# PROC.net
KiCad netlist of a schematic drawn in Altium Designer
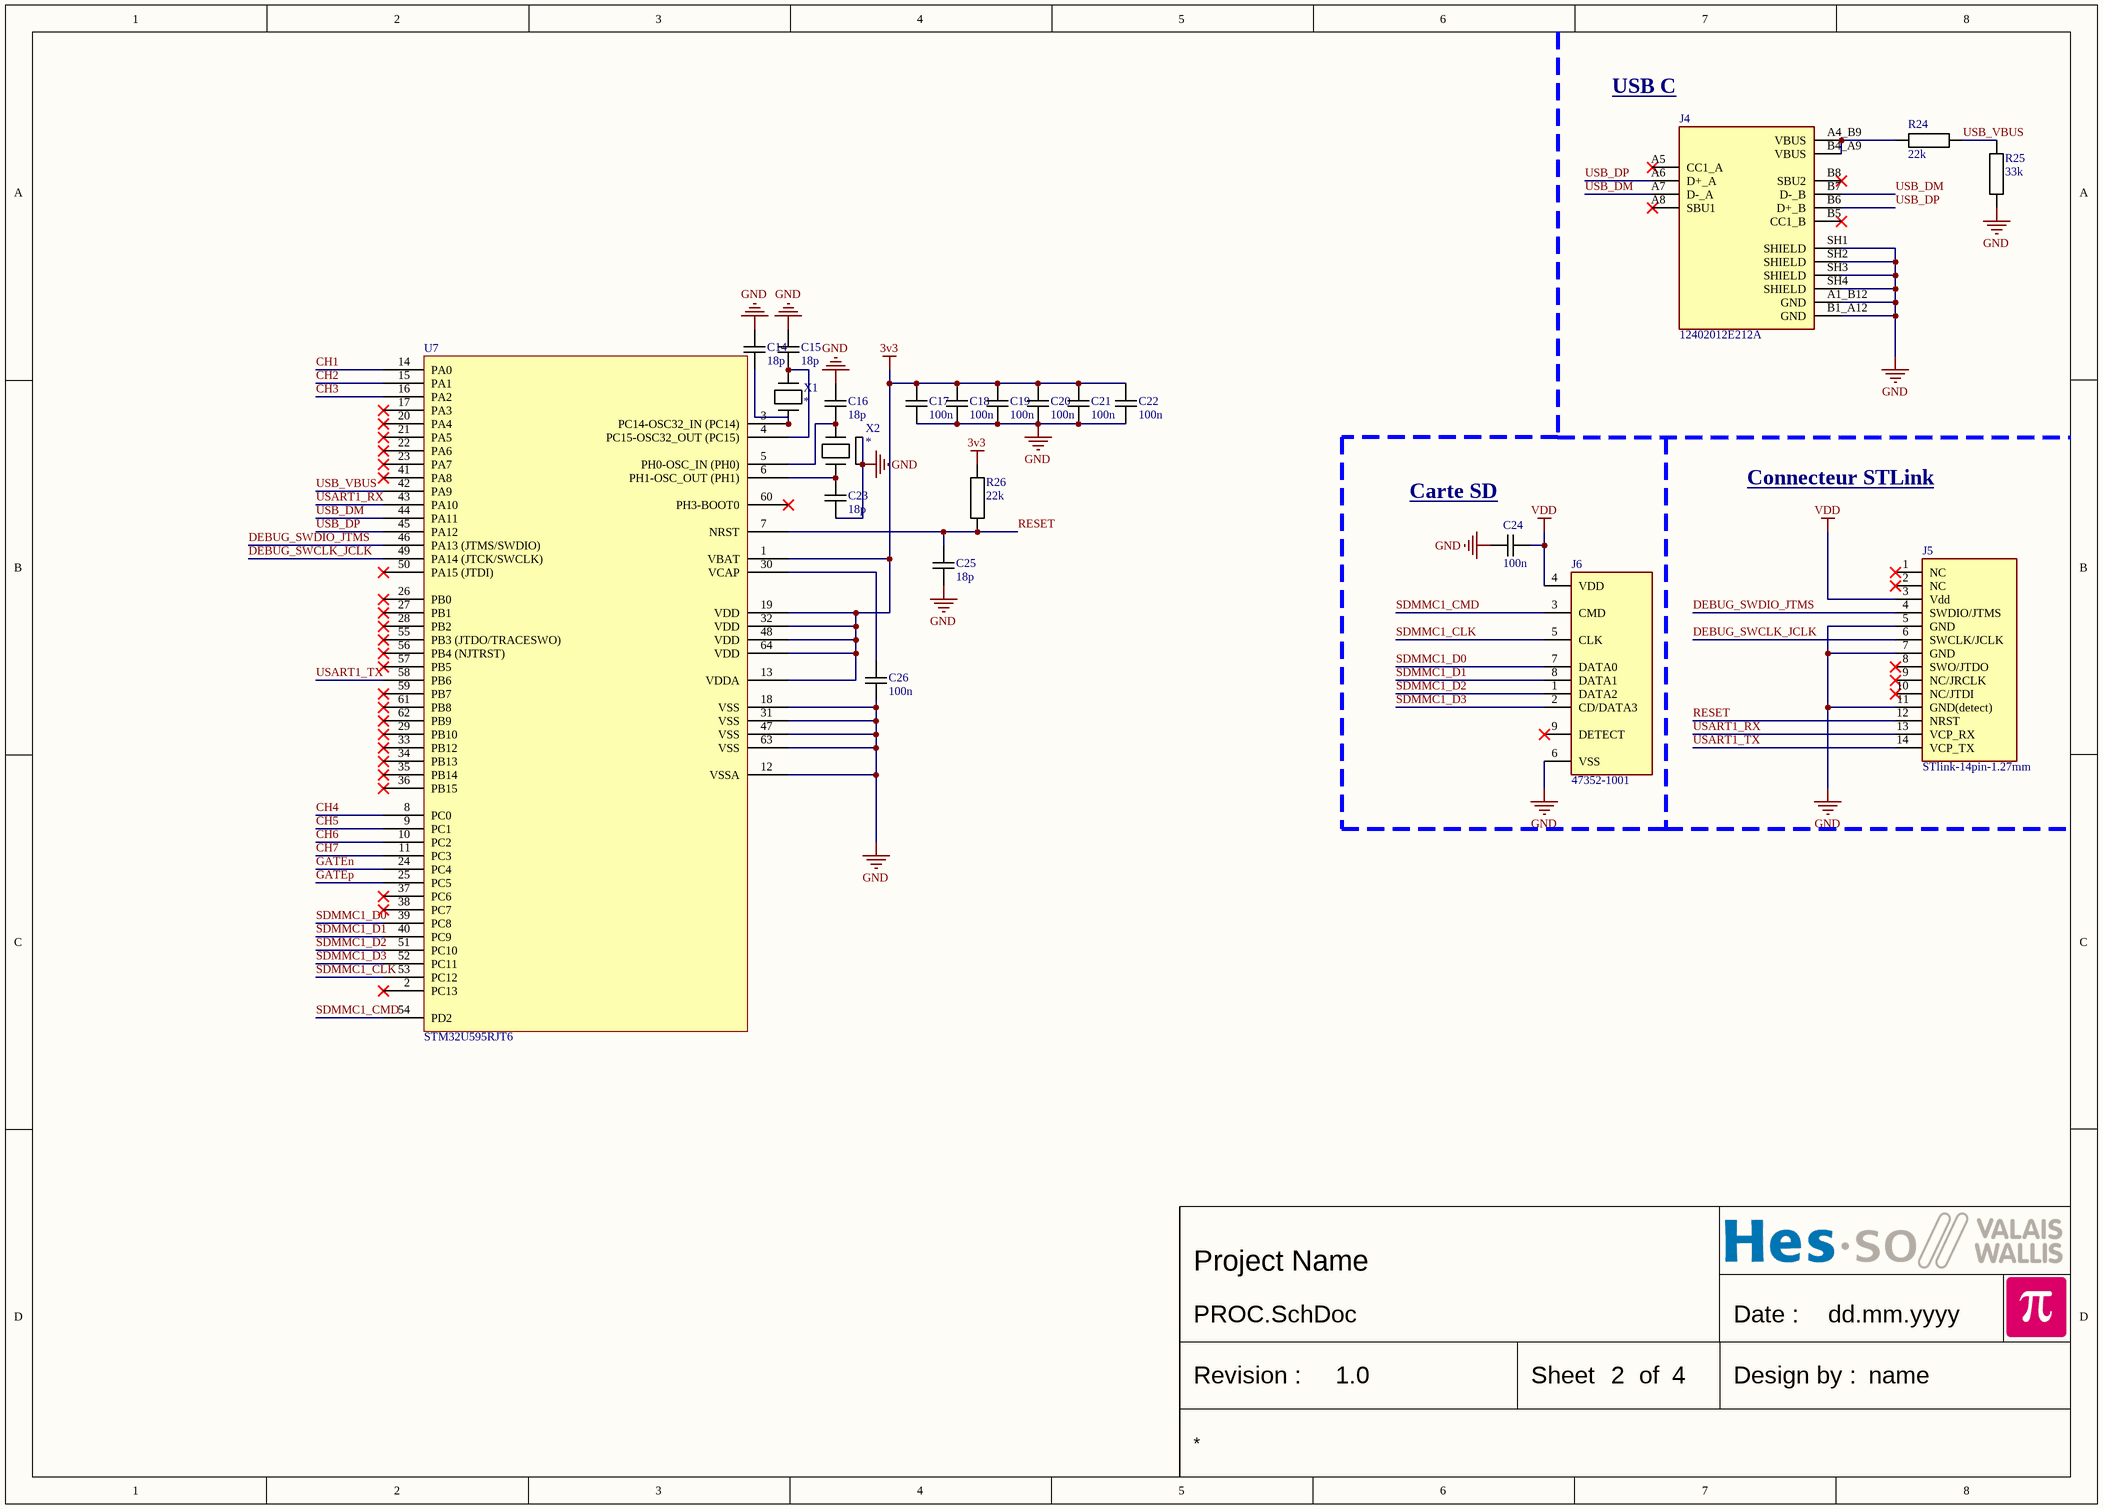
[diagram p0: PROC.SchDoc]

(export (version "E")
  (design (tool "Eeschema 10.0.6"))
  (components
    (comp (ref "C14")
      (value "18p")
      (footprint "CAPACITOR 1005 REFLOW")
      (description "Capacitor")
      (libsource (lib "Capacitor") (part "Capacitor"))
    )
    (comp (ref "C15")
      (value "18p")
      (footprint "CAPACITOR 1005 REFLOW")
      (description "Capacitor")
      (libsource (lib "Capacitor") (part "Capacitor"))
    )
    (comp (ref "C16")
      (value "18p")
      (footprint "CAPACITOR 1005 REFLOW")
      (description "Capacitor")
      (libsource (lib "Capacitor") (part "Capacitor"))
    )
    (comp (ref "C17")
      (value "100n")
      (footprint "CAPACITOR 1005 REFLOW")
      (description "Capacitor")
      (libsource (lib "Capacitor") (part "Capacitor"))
    )
    (comp (ref "C18")
      (value "100n")
      (footprint "CAPACITOR 1005 REFLOW")
      (description "Capacitor")
      (libsource (lib "Capacitor") (part "Capacitor"))
    )
    (comp (ref "C19")
      (value "100n")
      (footprint "CAPACITOR 1005 REFLOW")
      (description "Capacitor")
      (libsource (lib "Capacitor") (part "Capacitor"))
    )
    (comp (ref "C20")
      (value "100n")
      (footprint "CAPACITOR 1005 REFLOW")
      (description "Capacitor")
      (libsource (lib "Capacitor") (part "Capacitor"))
    )
    (comp (ref "C21")
      (value "100n")
      (footprint "CAPACITOR 1005 REFLOW")
      (description "Capacitor")
      (libsource (lib "Capacitor") (part "Capacitor"))
    )
    (comp (ref "C22")
      (value "100n")
      (footprint "CAPACITOR 1005 REFLOW")
      (description "Capacitor")
      (libsource (lib "Capacitor") (part "Capacitor"))
    )
    (comp (ref "C23")
      (value "18p")
      (footprint "CAPACITOR 1005 REFLOW")
      (description "Capacitor")
      (libsource (lib "Capacitor") (part "Capacitor"))
    )
    (comp (ref "C24")
      (value "100n")
      (footprint "CAPACITOR 1005 REFLOW")
      (description "Capacitor")
      (libsource (lib "Capacitor") (part "Capacitor"))
    )
    (comp (ref "C25")
      (value "18p")
      (footprint "CAPACITOR 1005 REFLOW")
      (description "Capacitor")
      (libsource (lib "Capacitor") (part "Capacitor"))
    )
    (comp (ref "C26")
      (value "100n")
      (footprint "CAPACITOR 1005 REFLOW")
      (description "Capacitor")
      (libsource (lib "Capacitor") (part "Capacitor"))
    )
    (comp (ref "J4")
      (value "12402012E212A")
      (footprint "USB-C-SMD Amphenol 12402012E212A")
      (description "USB-C-SMD Amphenol 12402012E212A")
      (libsource (lib "Connector") (part "USB-C-SMD Amphenol 12402012E212A"))
    )
    (comp (ref "J5")
      (value "STlink-14pin-1.27mm")
      (footprint "FTSH-107-01-S-D-K")
      (libsource (lib "Connector") (part "STlink-14pin-1.27mm"))
    )
    (comp (ref "J6")
      (value "47352-1001")
      (footprint "SD MICRO MOLEX 47352-1001")
      (description "SD Card  Micro")
      (libsource (lib "Connector") (part "SD-MICRO MOLEX 47352-1001"))
    )
    (comp (ref "R24")
      (value "22k")
      (footprint "RESISTOR 1005 REFLOW")
      (description "Resistor")
      (libsource (lib "Resistor") (part "Resistor"))
    )
    (comp (ref "R25")
      (value "33k")
      (footprint "RESISTOR 1005 REFLOW")
      (description "Resistor")
      (libsource (lib "Resistor") (part "Resistor"))
    )
    (comp (ref "R26")
      (value "22k")
      (footprint "RESISTOR 1005 REFLOW")
      (description "Resistor")
      (libsource (lib "Resistor") (part "Resistor"))
    )
    (comp (ref "U7")
      (value "STM32U595RJT6")
      (footprint "TSQFP50P1200X1200X160-64N")
      (libsource (lib "STM") (part "STM32U595RJT6"))
    )
    (comp (ref "X1")
      (value "*")
      (footprint "Crystal C3.2x1.5 Abracon ABS07")
      (description "Crystal C3.2x1.5 Abracon ABS07")
      (libsource (lib "Oscillator") (part "Crystal C3.2x1.5 Abracon ABS07"))
    )
    (comp (ref "X2")
      (value "*")
      (footprint "Crystal C2.0x1.6 Kyocera CX2016DB")
      (description "Crystal C2.0x1.6 Kyocera CX2016DB")
      (libsource (lib "Oscillator") (part "Crystal C2.0x1.6 Kyocera CX2016DB"))
    )
  )
  (nets
    (net (code "1") (name "/CH1") (class "Default")
      (node (ref "U7") (pin "14") (pinfunction "PA0_14") (pintype "passive"))
    )
    (net (code "2") (name "/CH2") (class "Default")
      (node (ref "U7") (pin "15") (pinfunction "PA1_15") (pintype "passive"))
    )
    (net (code "3") (name "/CH3") (class "Default")
      (node (ref "U7") (pin "16") (pinfunction "PA2_16") (pintype "passive"))
    )
    (net (code "4") (name "/CH4") (class "Default")
      (node (ref "U7") (pin "8") (pinfunction "PC0_8") (pintype "passive"))
    )
    (net (code "5") (name "/CH5") (class "Default")
      (node (ref "U7") (pin "9") (pinfunction "PC1_9") (pintype "passive"))
    )
    (net (code "6") (name "/CH6") (class "Default")
      (node (ref "U7") (pin "10") (pinfunction "PC2_10") (pintype "passive"))
    )
    (net (code "7") (name "/CH7") (class "Default")
      (node (ref "U7") (pin "11") (pinfunction "PC3_11") (pintype "passive"))
    )
    (net (code "8") (name "/DEBUG_SWCLK_JCLK") (class "Default")
      (node (ref "J5") (pin "6") (pinfunction "SWCLK/JCLK_6") (pintype "passive"))
      (node (ref "U7") (pin "49") (pinfunction "PA14_(JTCK/SWCLK)_49") (pintype "passive"))
    )
    (net (code "9") (name "/DEBUG_SWDIO_JTMS") (class "Default")
      (node (ref "J5") (pin "4") (pinfunction "SWDIO/JTMS_4") (pintype "passive"))
      (node (ref "U7") (pin "46") (pinfunction "PA13_(JTMS/SWDIO)_46") (pintype "passive"))
    )
    (net (code "10") (name "/GATEn") (class "Default")
      (node (ref "U7") (pin "24") (pinfunction "PC4_24") (pintype "passive"))
    )
    (net (code "11") (name "/GATEp") (class "Default")
      (node (ref "U7") (pin "25") (pinfunction "PC5_25") (pintype "passive"))
    )
    (net (code "12") (name "/RESET") (class "Default")
      (node (ref "C25") (pin "1") (pinfunction "1_1") (pintype "passive"))
      (node (ref "J5") (pin "12") (pinfunction "NRST_12") (pintype "passive"))
      (node (ref "R26") (pin "1") (pinfunction "1_1") (pintype "passive"))
      (node (ref "U7") (pin "7") (pinfunction "NRST_7") (pintype "passive"))
    )
    (net (code "13") (name "/SDMMC1_CLK") (class "Default")
      (node (ref "J6") (pin "5") (pinfunction "CLK_5") (pintype "passive"))
      (node (ref "U7") (pin "53") (pinfunction "PC12_53") (pintype "passive"))
    )
    (net (code "14") (name "/SDMMC1_CMD") (class "Default")
      (node (ref "J6") (pin "3") (pinfunction "CMD_3") (pintype "passive"))
      (node (ref "U7") (pin "54") (pinfunction "PD2_54") (pintype "passive"))
    )
    (net (code "15") (name "/SDMMC1_D0") (class "Default")
      (node (ref "J6") (pin "7") (pinfunction "DATA0_7") (pintype "passive"))
      (node (ref "U7") (pin "39") (pinfunction "PC8_39") (pintype "passive"))
    )
    (net (code "16") (name "/SDMMC1_D1") (class "Default")
      (node (ref "J6") (pin "8") (pinfunction "DATA1_8") (pintype "passive"))
      (node (ref "U7") (pin "40") (pinfunction "PC9_40") (pintype "passive"))
    )
    (net (code "17") (name "/SDMMC1_D2") (class "Default")
      (node (ref "J6") (pin "1") (pinfunction "DATA2_1") (pintype "passive"))
      (node (ref "U7") (pin "51") (pinfunction "PC10_51") (pintype "passive"))
    )
    (net (code "18") (name "/SDMMC1_D3") (class "Default")
      (node (ref "J6") (pin "2") (pinfunction "CD/DATA3_2") (pintype "passive"))
      (node (ref "U7") (pin "52") (pinfunction "PC11_52") (pintype "passive"))
    )
    (net (code "19") (name "/USART1_RX") (class "Default")
      (node (ref "J5") (pin "13") (pinfunction "VCP_RX_13") (pintype "passive"))
      (node (ref "U7") (pin "43") (pinfunction "PA10_43") (pintype "passive"))
    )
    (net (code "20") (name "/USART1_TX") (class "Default")
      (node (ref "J5") (pin "14") (pinfunction "VCP_TX_14") (pintype "passive"))
      (node (ref "U7") (pin "58") (pinfunction "PB6_58") (pintype "passive"))
    )
    (net (code "21") (name "/USB_DM") (class "Default")
      (node (ref "J4") (pin "A7") (pinfunction "D-_A_A7") (pintype "passive"))
      (node (ref "J4") (pin "B7") (pinfunction "D-_B_B7") (pintype "passive"))
      (node (ref "U7") (pin "44") (pinfunction "PA11_44") (pintype "passive"))
    )
    (net (code "22") (name "/USB_DP") (class "Default")
      (node (ref "J4") (pin "A6") (pinfunction "D+_A_A6") (pintype "passive"))
      (node (ref "J4") (pin "B6") (pinfunction "D+_B_B6") (pintype "passive"))
      (node (ref "U7") (pin "45") (pinfunction "PA12_45") (pintype "passive"))
    )
    (net (code "23") (name "/USB_VBUS") (class "Default")
      (node (ref "R24") (pin "2") (pinfunction "2_2") (pintype "passive"))
      (node (ref "R25") (pin "2") (pinfunction "2_2") (pintype "passive"))
      (node (ref "U7") (pin "42") (pinfunction "PA9_42") (pintype "passive"))
    )
    (net (code "24") (name "3v3") (class "Default")
      (node (ref "C17") (pin "1") (pinfunction "1_1") (pintype "passive"))
      (node (ref "C18") (pin "1") (pinfunction "1_1") (pintype "passive"))
      (node (ref "C19") (pin "1") (pinfunction "1_1") (pintype "passive"))
      (node (ref "C20") (pin "1") (pinfunction "1_1") (pintype "passive"))
      (node (ref "C21") (pin "1") (pinfunction "1_1") (pintype "passive"))
      (node (ref "C22") (pin "1") (pinfunction "1_1") (pintype "passive"))
      (node (ref "R26") (pin "2") (pinfunction "2_2") (pintype "passive"))
      (node (ref "U7") (pin "1") (pinfunction "VBAT_1") (pintype "passive"))
      (node (ref "U7") (pin "13") (pinfunction "VDDA_13") (pintype "passive"))
      (node (ref "U7") (pin "19") (pinfunction "VDD_19") (pintype "passive"))
      (node (ref "U7") (pin "32") (pinfunction "VDD_32") (pintype "passive"))
      (node (ref "U7") (pin "48") (pinfunction "VDD_48") (pintype "passive"))
      (node (ref "U7") (pin "64") (pinfunction "VDD_64") (pintype "passive"))
    )
    (net (code "25") (name "GND") (class "Default")
      (node (ref "C14") (pin "1") (pinfunction "1_1") (pintype "passive"))
      (node (ref "C15") (pin "1") (pinfunction "1_1") (pintype "passive"))
      (node (ref "C16") (pin "1") (pinfunction "1_1") (pintype "passive"))
      (node (ref "C17") (pin "2") (pinfunction "2_2") (pintype "passive"))
      (node (ref "C18") (pin "2") (pinfunction "2_2") (pintype "passive"))
      (node (ref "C19") (pin "2") (pinfunction "2_2") (pintype "passive"))
      (node (ref "C20") (pin "2") (pinfunction "2_2") (pintype "passive"))
      (node (ref "C21") (pin "2") (pinfunction "2_2") (pintype "passive"))
      (node (ref "C22") (pin "2") (pinfunction "2_2") (pintype "passive"))
      (node (ref "C23") (pin "2") (pinfunction "2_2") (pintype "passive"))
      (node (ref "C24") (pin "2") (pinfunction "2_2") (pintype "passive"))
      (node (ref "C25") (pin "2") (pinfunction "2_2") (pintype "passive"))
      (node (ref "C26") (pin "2") (pinfunction "2_2") (pintype "passive"))
      (node (ref "J4") (pin "A1_B12") (pinfunction "GND_A1_B12") (pintype "passive"))
      (node (ref "J4") (pin "B1_A12") (pinfunction "GND_B1_A12") (pintype "passive"))
      (node (ref "J4") (pin "SH1") (pinfunction "SHIELD_SH1") (pintype "passive"))
      (node (ref "J4") (pin "SH2") (pinfunction "SHIELD_SH2") (pintype "passive"))
      (node (ref "J4") (pin "SH3") (pinfunction "SHIELD_SH3") (pintype "passive"))
      (node (ref "J4") (pin "SH4") (pinfunction "SHIELD_SH4") (pintype "passive"))
      (node (ref "J5") (pin "11") (pinfunction "GND(detect)_11") (pintype "passive"))
      (node (ref "J5") (pin "5") (pinfunction "GND_5") (pintype "passive"))
      (node (ref "J5") (pin "7") (pinfunction "GND_7") (pintype "passive"))
      (node (ref "J6") (pin "6") (pinfunction "VSS_6") (pintype "passive"))
      (node (ref "R25") (pin "1") (pinfunction "1_1") (pintype "passive"))
      (node (ref "U7") (pin "12") (pinfunction "VSSA_12") (pintype "passive"))
      (node (ref "U7") (pin "18") (pinfunction "VSS_18") (pintype "passive"))
      (node (ref "U7") (pin "31") (pinfunction "VSS_31") (pintype "passive"))
      (node (ref "U7") (pin "47") (pinfunction "VSS_47") (pintype "passive"))
      (node (ref "U7") (pin "63") (pinfunction "VSS_63") (pintype "passive"))
      (node (ref "X2") (pin "2") (pinfunction "2_2") (pintype "passive"))
      (node (ref "X2") (pin "4") (pinfunction "4_4") (pintype "passive"))
    )
    (net (code "26") (name "Net-(J4-VBUS-PadA4_B9)") (class "Default")
      (node (ref "J4") (pin "A4_B9") (pinfunction "VBUS_A4_B9") (pintype "passive"))
      (node (ref "J4") (pin "B4_A9") (pinfunction "VBUS_B4_A9") (pintype "passive"))
      (node (ref "R24") (pin "1") (pinfunction "1_1") (pintype "passive"))
    )
    (net (code "27") (name "Net-(U7-PC14-OSC32_IN_(PC14))") (class "Default")
      (node (ref "C14") (pin "2") (pinfunction "2_2") (pintype "passive"))
      (node (ref "U7") (pin "3") (pinfunction "PC14-OSC32_IN_(PC14)_3") (pintype "passive"))
      (node (ref "X1") (pin "1") (pinfunction "1_1") (pintype "passive"))
    )
    (net (code "28") (name "Net-(U7-PC15-OSC32_OUT_(PC15))") (class "Default")
      (node (ref "C15") (pin "2") (pinfunction "2_2") (pintype "passive"))
      (node (ref "U7") (pin "4") (pinfunction "PC15-OSC32_OUT_(PC15)_4") (pintype "passive"))
      (node (ref "X1") (pin "2") (pinfunction "2_2") (pintype "passive"))
    )
    (net (code "29") (name "Net-(U7-PH0-OSC_IN_(PH0))") (class "Default")
      (node (ref "C16") (pin "2") (pinfunction "2_2") (pintype "passive"))
      (node (ref "U7") (pin "5") (pinfunction "PH0-OSC_IN_(PH0)_5") (pintype "passive"))
      (node (ref "X2") (pin "3") (pinfunction "3_3") (pintype "passive"))
    )
    (net (code "30") (name "Net-(U7-PH1-OSC_OUT_(PH1))") (class "Default")
      (node (ref "C23") (pin "1") (pinfunction "1_1") (pintype "passive"))
      (node (ref "U7") (pin "6") (pinfunction "PH1-OSC_OUT_(PH1)_6") (pintype "passive"))
      (node (ref "X2") (pin "1") (pinfunction "1_1") (pintype "passive"))
    )
    (net (code "31") (name "Net-(U7-VCAP)") (class "Default")
      (node (ref "C26") (pin "1") (pinfunction "1_1") (pintype "passive"))
      (node (ref "U7") (pin "30") (pinfunction "VCAP_30") (pintype "passive"))
    )
    (net (code "32") (name "VDD") (class "Default")
      (node (ref "C24") (pin "1") (pinfunction "1_1") (pintype "passive"))
      (node (ref "J5") (pin "3") (pinfunction "Vdd_3") (pintype "passive"))
      (node (ref "J6") (pin "4") (pinfunction "VDD_4") (pintype "passive"))
    )
    (net (code "33") (name "unconnected-(J4-CC1_A-PadA5)") (class "Default")
      (node (ref "J4") (pin "A5") (pinfunction "CC1_A_A5") (pintype "passive+no_connect"))
    )
    (net (code "34") (name "unconnected-(J4-CC1_B-PadB5)") (class "Default")
      (node (ref "J4") (pin "B5") (pinfunction "CC1_B_B5") (pintype "passive+no_connect"))
    )
    (net (code "35") (name "unconnected-(J4-SBU1-PadA8)") (class "Default")
      (node (ref "J4") (pin "A8") (pinfunction "SBU1_A8") (pintype "passive+no_connect"))
    )
    (net (code "36") (name "unconnected-(J4-SBU2-PadB8)") (class "Default")
      (node (ref "J4") (pin "B8") (pinfunction "SBU2_B8") (pintype "passive+no_connect"))
    )
    (net (code "37") (name "unconnected-(J5-NC-Pad1)") (class "Default")
      (node (ref "J5") (pin "1") (pinfunction "NC_1") (pintype "passive+no_connect"))
    )
    (net (code "38") (name "unconnected-(J5-NC-Pad2)") (class "Default")
      (node (ref "J5") (pin "2") (pinfunction "NC_2") (pintype "passive+no_connect"))
    )
    (net (code "39") (name "unconnected-(J5-NC{slash}JRCLK-Pad9)") (class "Default")
      (node (ref "J5") (pin "9") (pinfunction "NC/JRCLK_9") (pintype "passive+no_connect"))
    )
    (net (code "40") (name "unconnected-(J5-NC{slash}JTDI-Pad10)") (class "Default")
      (node (ref "J5") (pin "10") (pinfunction "NC/JTDI_10") (pintype "passive+no_connect"))
    )
    (net (code "41") (name "unconnected-(J5-SWO{slash}JTDO-Pad8)") (class "Default")
      (node (ref "J5") (pin "8") (pinfunction "SWO/JTDO_8") (pintype "passive+no_connect"))
    )
    (net (code "42") (name "unconnected-(J6-DETECT-Pad9)") (class "Default")
      (node (ref "J6") (pin "9") (pinfunction "DETECT_9") (pintype "passive+no_connect"))
    )
    (net (code "43") (name "unconnected-(U7-PA3-Pad17)") (class "Default")
      (node (ref "U7") (pin "17") (pinfunction "PA3_17") (pintype "passive+no_connect"))
    )
    (net (code "44") (name "unconnected-(U7-PA4-Pad20)") (class "Default")
      (node (ref "U7") (pin "20") (pinfunction "PA4_20") (pintype "passive+no_connect"))
    )
    (net (code "45") (name "unconnected-(U7-PA5-Pad21)") (class "Default")
      (node (ref "U7") (pin "21") (pinfunction "PA5_21") (pintype "passive+no_connect"))
    )
    (net (code "46") (name "unconnected-(U7-PA6-Pad22)") (class "Default")
      (node (ref "U7") (pin "22") (pinfunction "PA6_22") (pintype "passive+no_connect"))
    )
    (net (code "47") (name "unconnected-(U7-PA7-Pad23)") (class "Default")
      (node (ref "U7") (pin "23") (pinfunction "PA7_23") (pintype "passive+no_connect"))
    )
    (net (code "48") (name "unconnected-(U7-PA8-Pad41)") (class "Default")
      (node (ref "U7") (pin "41") (pinfunction "PA8_41") (pintype "passive+no_connect"))
    )
    (net (code "49") (name "unconnected-(U7-PA15_(JTDI)-Pad50)") (class "Default")
      (node (ref "U7") (pin "50") (pinfunction "PA15_(JTDI)_50") (pintype "passive+no_connect"))
    )
    (net (code "50") (name "unconnected-(U7-PB0-Pad26)") (class "Default")
      (node (ref "U7") (pin "26") (pinfunction "PB0_26") (pintype "passive+no_connect"))
    )
    (net (code "51") (name "unconnected-(U7-PB1-Pad27)") (class "Default")
      (node (ref "U7") (pin "27") (pinfunction "PB1_27") (pintype "passive+no_connect"))
    )
    (net (code "52") (name "unconnected-(U7-PB2-Pad28)") (class "Default")
      (node (ref "U7") (pin "28") (pinfunction "PB2_28") (pintype "passive+no_connect"))
    )
    (net (code "53") (name "unconnected-(U7-PB3_(JTDO{slash}TRACESWO)-Pad55)") (class "Default")
      (node (ref "U7") (pin "55") (pinfunction "PB3_(JTDO/TRACESWO)_55") (pintype "passive+no_connect"))
    )
    (net (code "54") (name "unconnected-(U7-PB4_(NJTRST)-Pad56)") (class "Default")
      (node (ref "U7") (pin "56") (pinfunction "PB4_(NJTRST)_56") (pintype "passive+no_connect"))
    )
    (net (code "55") (name "unconnected-(U7-PB5-Pad57)") (class "Default")
      (node (ref "U7") (pin "57") (pinfunction "PB5_57") (pintype "passive+no_connect"))
    )
    (net (code "56") (name "unconnected-(U7-PB7-Pad59)") (class "Default")
      (node (ref "U7") (pin "59") (pinfunction "PB7_59") (pintype "passive+no_connect"))
    )
    (net (code "57") (name "unconnected-(U7-PB8-Pad61)") (class "Default")
      (node (ref "U7") (pin "61") (pinfunction "PB8_61") (pintype "passive+no_connect"))
    )
    (net (code "58") (name "unconnected-(U7-PB9-Pad62)") (class "Default")
      (node (ref "U7") (pin "62") (pinfunction "PB9_62") (pintype "passive+no_connect"))
    )
    (net (code "59") (name "unconnected-(U7-PB10-Pad29)") (class "Default")
      (node (ref "U7") (pin "29") (pinfunction "PB10_29") (pintype "passive+no_connect"))
    )
    (net (code "60") (name "unconnected-(U7-PB12-Pad33)") (class "Default")
      (node (ref "U7") (pin "33") (pinfunction "PB12_33") (pintype "passive+no_connect"))
    )
    (net (code "61") (name "unconnected-(U7-PB13-Pad34)") (class "Default")
      (node (ref "U7") (pin "34") (pinfunction "PB13_34") (pintype "passive+no_connect"))
    )
    (net (code "62") (name "unconnected-(U7-PB14-Pad35)") (class "Default")
      (node (ref "U7") (pin "35") (pinfunction "PB14_35") (pintype "passive+no_connect"))
    )
    (net (code "63") (name "unconnected-(U7-PB15-Pad36)") (class "Default")
      (node (ref "U7") (pin "36") (pinfunction "PB15_36") (pintype "passive+no_connect"))
    )
    (net (code "64") (name "unconnected-(U7-PC6-Pad37)") (class "Default")
      (node (ref "U7") (pin "37") (pinfunction "PC6_37") (pintype "passive+no_connect"))
    )
    (net (code "65") (name "unconnected-(U7-PC7-Pad38)") (class "Default")
      (node (ref "U7") (pin "38") (pinfunction "PC7_38") (pintype "passive+no_connect"))
    )
    (net (code "66") (name "unconnected-(U7-PC13-Pad2)") (class "Default")
      (node (ref "U7") (pin "2") (pinfunction "PC13_2") (pintype "passive+no_connect"))
    )
    (net (code "67") (name "unconnected-(U7-PH3-BOOT0-Pad60)") (class "Default")
      (node (ref "U7") (pin "60") (pinfunction "PH3-BOOT0_60") (pintype "passive+no_connect"))
    )
  )
)
